# TOP_-_NAATOS_INLAY.net
KiCad netlist of a schematic drawn in Altium Designer
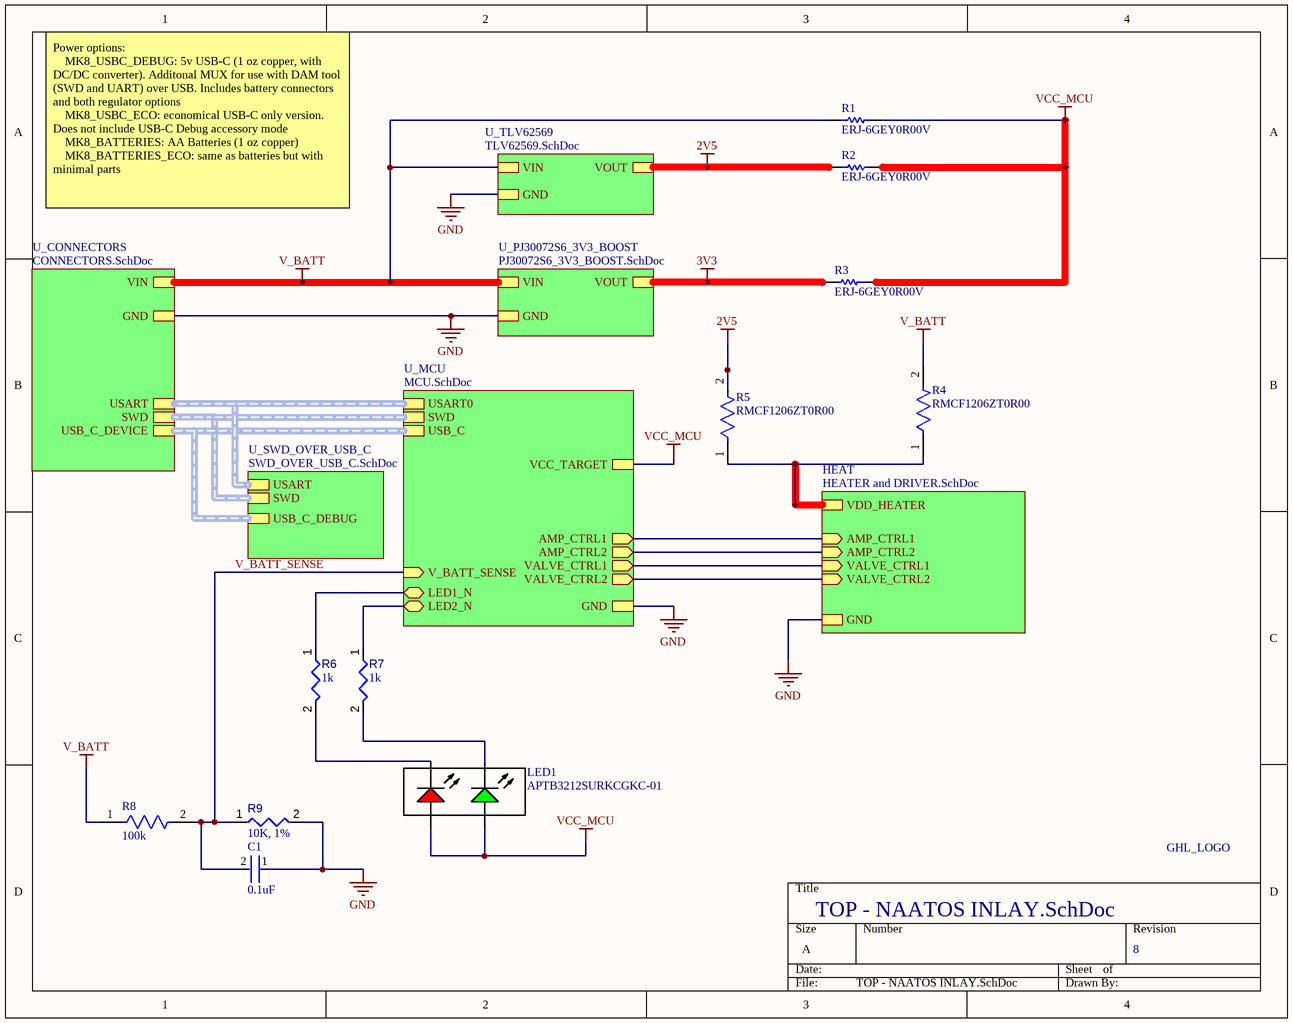
[diagram p0: TOP - NAATOS INLAY.SchDoc]

(export (version "E")
  (design (tool "Eeschema 10.0.6"))
  (components
    (comp (ref "C1")
      (value "0.1uF")
      (footprint "FP-CL17-IPC_C")
      (description "Cap Ceramic 100nF 10V X7R ±10% SMD 0402 +125°C Paper T/R")
      (fields (field (name "TOLERANCE") "10%"))
      (libsource (lib "Altium Content Vault") (part "b4654b650e69147ec39a6b967a45e02"))
    )
    (comp (ref "LED1")
      (value "APTB3212SURKCGKC-01")
      (footprint "APTB3212SURKCGKC-01")
      (description "Dual Color LED")
      (fields (field (name "MANUFACTURER") "Kingbright"))
      (libsource (lib "APTB3212SURKCGKC-01") (part "APTB3212SURKCGKC-01"))
    )
    (comp (ref "LOGO1")
      (value "GHL_LOGO")
      (footprint "GHLABS_LOGO")
      (libsource (lib "Global Health Labs, Inc") (part "GHL_LOGO"))
    )
    (comp (ref "R1")
      (value "ERJ-6GEY0R00V")
      (footprint "RESC2013X70X40NL20T20")
      (description "Chip Resistor, 0 Ohm, +/- 1%, 0.125 W, -55 to 155 degC, 0805 (2012 Metric), RoHS, Tape and Reel")
      (fields (field (name "TOLERANCE") "5%"))
      (libsource (lib "Altium Content Vault") (part "RES-2"))
    )
    (comp (ref "R2")
      (value "ERJ-6GEY0R00V")
      (footprint "RESC2013X70X40NL20T20")
      (description "Chip Resistor, 0 Ohm, +/- 1%, 0.125 W, -55 to 155 degC, 0805 (2012 Metric), RoHS, Tape and Reel")
      (fields (field (name "TOLERANCE") "5%"))
      (libsource (lib "Altium Content Vault") (part "RES-2"))
    )
    (comp (ref "R3")
      (value "ERJ-6GEY0R00V")
      (footprint "RESC2013X70X40NL20T20")
      (description "Chip Resistor, 0 Ohm, +/- 1%, 0.125 W, -55 to 155 degC, 0805 (2012 Metric), RoHS, Tape and Reel")
      (fields (field (name "TOLERANCE") "5%"))
      (libsource (lib "Altium Content Vault") (part "RES-2"))
    )
    (comp (ref "R4")
      (value "RMCF1206ZT0R00")
      (footprint "FP-RMCF1206-MFG")
      (description "0Ω ±0 0.25W 1206 Thick Film Chip Resistor AEC-Q200 compliant")
      (libsource (lib "Altium Content Vault") (part "1029c3af85768c4190bb7ad29bc67b5"))
    )
    (comp (ref "R5")
      (value "RMCF1206ZT0R00")
      (footprint "FP-RMCF1206-MFG")
      (description "0Ω ±0 0.25W 1206 Thick Film Chip Resistor AEC-Q200 compliant")
      (libsource (lib "Altium Content Vault") (part "1029c3af85768c4190bb7ad29bc67b5"))
    )
    (comp (ref "R6")
      (value "1k")
      (footprint "RESC1608X55X25ML10T15")
      (description "Chip Resistor, 1 KOhm, +/-1%, 0.1 W, -55 to 155 degC, 0603 (1608 Metric)")
      (fields (field (name "POWER") "100mW") (field (name "TOLERANCE") "1%"))
      (libsource (lib "Global Health Labs, Inc") (part "RES-2"))
    )
    (comp (ref "R7")
      (value "1k")
      (footprint "RESC1608X55X25ML10T15")
      (description "Chip Resistor, 1 KOhm, +/-1%, 0.1 W, -55 to 155 degC, 0603 (1608 Metric)")
      (fields (field (name "POWER") "100mW") (field (name "TOLERANCE") "1%"))
      (libsource (lib "Global Health Labs, Inc") (part "RES-2"))
    )
    (comp (ref "R8")
      (value "CRCW0402100KFKED")
      (footprint "FP-CRCW0402-e3-IPC_C")
      (description "RES Thick Film, 100kΩ, 1%, 0.063W, 100ppm/°C, 0402")
      (fields (field (name "RESISTANCE") "100k") (field (name "TOLERANCE") "1%"))
      (libsource (lib "Altium Content Vault") (part "1029c3af85768c4190bb7ad29bc67b5"))
    )
    (comp (ref "R9")
      (value "10K, 1%")
      (footprint "RESC0402(1005)_L")
      (description "Chip Resistor, 10 kOhms, +/-1 %, 63 mW, -55 to 125 degC, 0402")
      (fields (field (name "POWER") "63mW") (field (name "TOLERANCE") "1%"))
      (libsource (lib "Global Health Labs, Inc") (part "RES-2"))
    )
  )
  (nets
    (net (code "3") (name "/LED1_N") (class "Default")
      (node (ref "R6") (pin "1") (pinfunction "1_1") (pintype "passive"))
    )
    (net (code "4") (name "/LED2_N") (class "Default")
      (node (ref "R7") (pin "1") (pinfunction "1_1") (pintype "passive"))
    )
    (net (code "10") (name "/VDD_HEATER") (class "Default")
      (node (ref "R4") (pin "1") (pinfunction "1_1") (pintype "passive"))
      (node (ref "R5") (pin "1") (pinfunction "1_1") (pintype "passive"))
    )
    (net (code "11") (name "/V_BATT_SENSE") (class "Default")
      (node (ref "C1") (pin "2") (pinfunction "2_2") (pintype "passive"))
      (node (ref "R8") (pin "2") (pinfunction "2_2") (pintype "passive"))
      (node (ref "R9") (pin "1") (pinfunction "1_1") (pintype "passive"))
    )
    (net (code "12") (name "2V5") (class "Default")
      (node (ref "R2") (pin "1") (pinfunction "1_1") (pintype "passive"))
      (node (ref "R5") (pin "2") (pinfunction "2_2") (pintype "passive"))
    )
    (net (code "13") (name "3V3") (class "Default")
      (node (ref "R3") (pin "1") (pinfunction "1_1") (pintype "passive"))
    )
    (net (code "14") (name "GND") (class "Default")
      (node (ref "C1") (pin "1") (pinfunction "1_1") (pintype "passive"))
      (node (ref "R9") (pin "2") (pinfunction "2_2") (pintype "passive"))
    )
    (net (code "15") (name "Net-(LED1-K-Pad1)") (class "Default")
      (node (ref "LED1") (pin "1") (pinfunction "K_1") (pintype "passive"))
      (node (ref "R6") (pin "2") (pinfunction "2_2") (pintype "passive"))
    )
    (net (code "16") (name "Net-(LED1-K-Pad4)") (class "Default")
      (node (ref "LED1") (pin "4") (pinfunction "K_4") (pintype "passive"))
      (node (ref "R7") (pin "2") (pinfunction "2_2") (pintype "passive"))
    )
    (net (code "17") (name "VCC_MCU") (class "Default")
      (node (ref "LED1") (pin "2") (pinfunction "A_2") (pintype "passive"))
      (node (ref "LED1") (pin "3") (pinfunction "A_3") (pintype "passive"))
      (node (ref "R1") (pin "2") (pinfunction "2_2") (pintype "passive"))
      (node (ref "R2") (pin "2") (pinfunction "2_2") (pintype "passive"))
      (node (ref "R3") (pin "2") (pinfunction "2_2") (pintype "passive"))
    )
    (net (code "18") (name "V_BATT") (class "Default")
      (node (ref "R1") (pin "1") (pinfunction "1_1") (pintype "passive"))
      (node (ref "R4") (pin "2") (pinfunction "2_2") (pintype "passive"))
      (node (ref "R8") (pin "1") (pinfunction "1_1") (pintype "passive"))
    )
  )
)
